# M218A.net
KiCad netlist of a schematic drawn in EAGLE
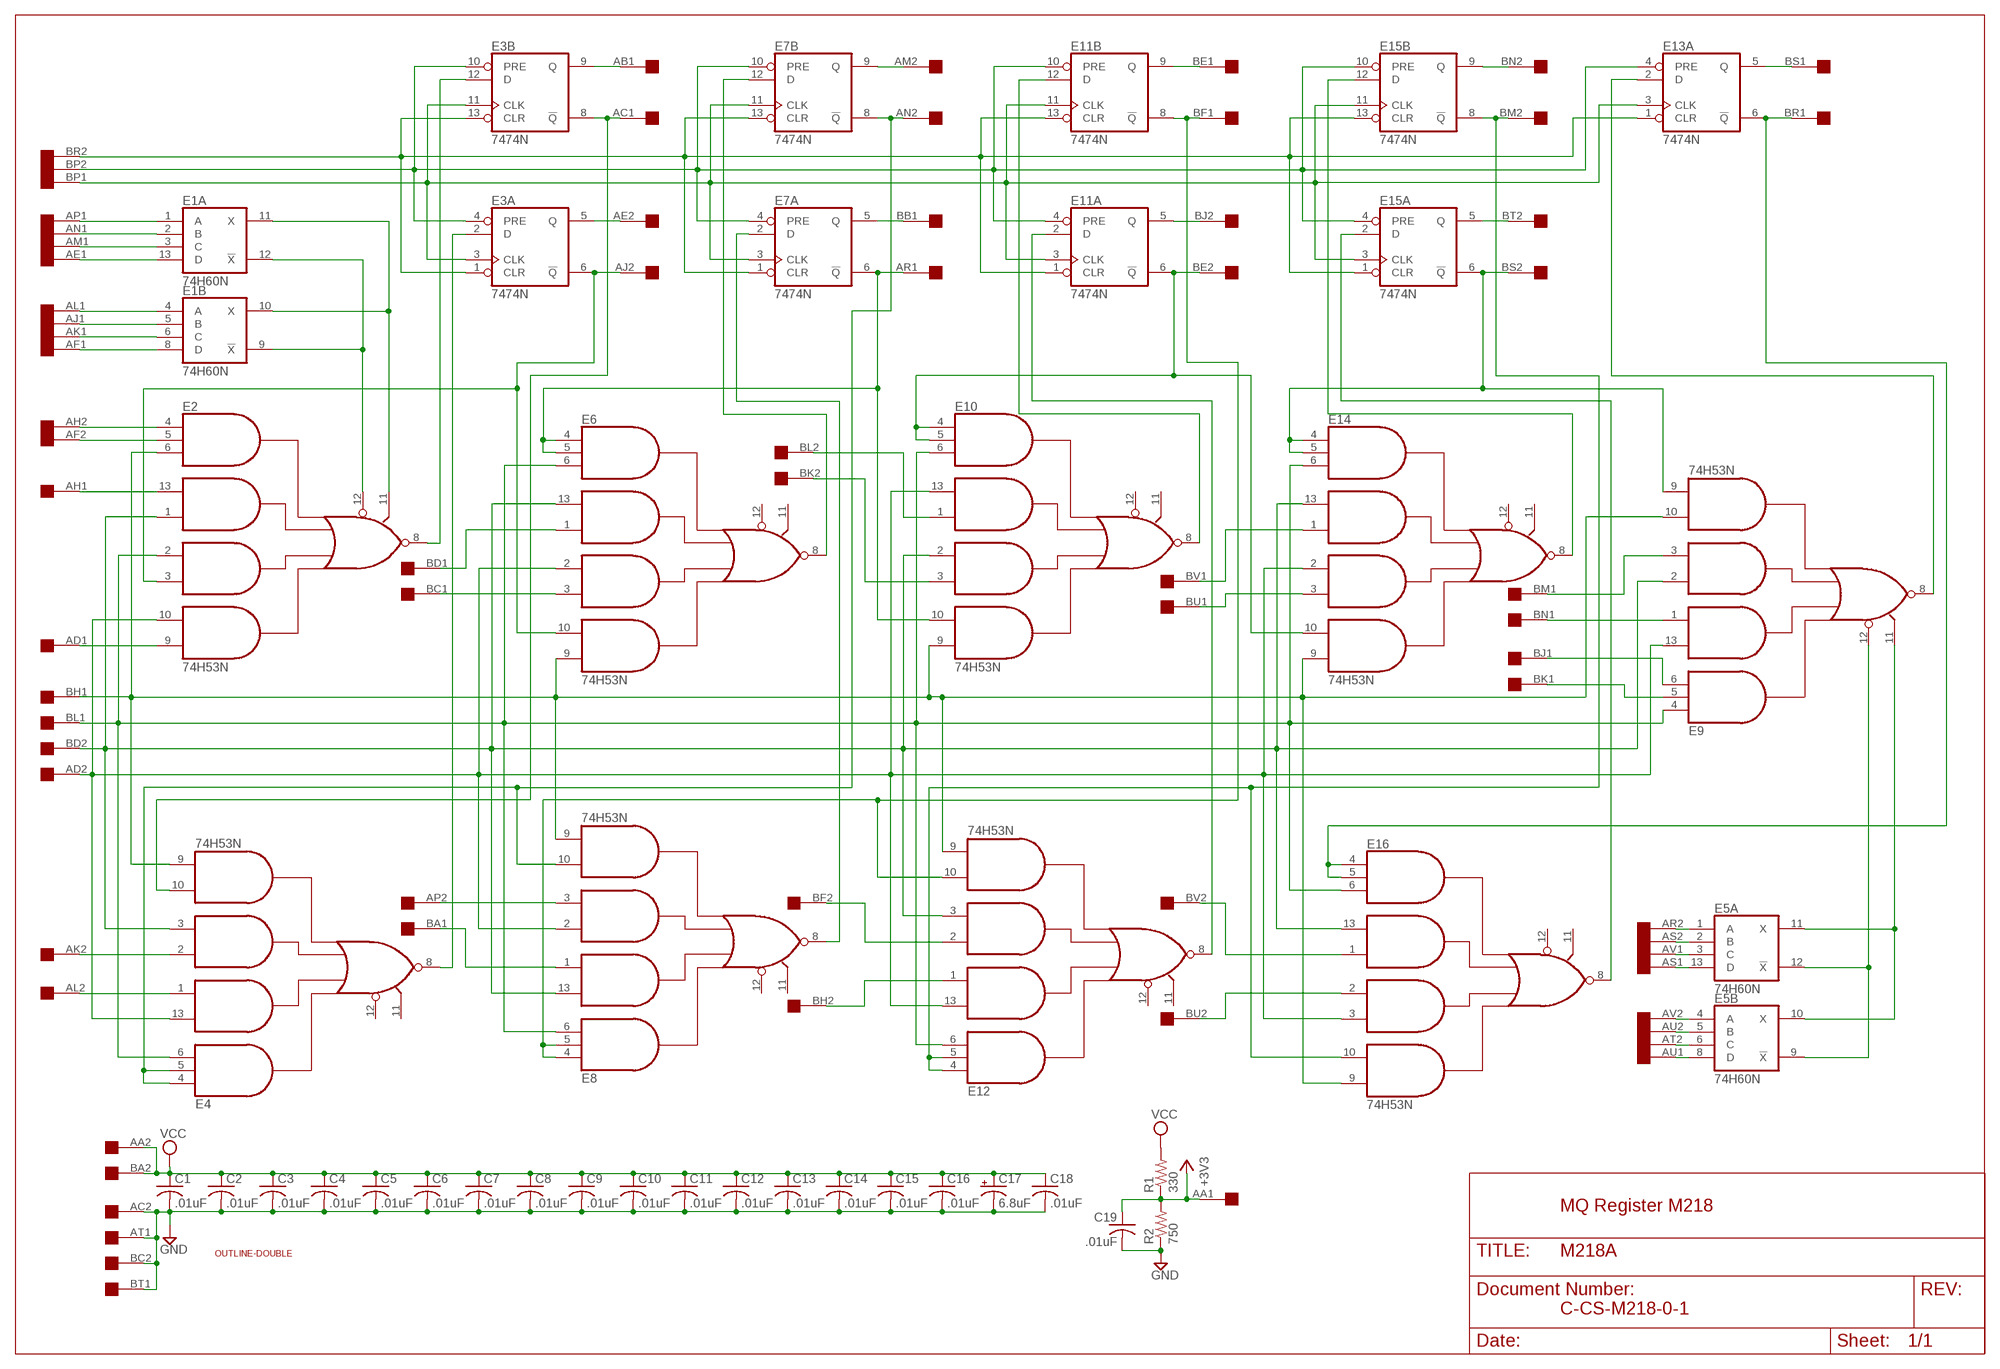
[diagram p0: schematic, sheet 1]

(export (version "E")
  (design (tool "Eeschema 10.0.6"))
  (components
    (comp (ref "C1")
      (value ".01uF")
      (footprint "eagle-import:C050-025X075")
      (libsource (lib "eagle-import") (part "C-US050-025X075"))
    )
    (comp (ref "C2")
      (value ".01uF")
      (footprint "eagle-import:C050-025X075")
      (libsource (lib "eagle-import") (part "C-US050-025X075"))
    )
    (comp (ref "C3")
      (value ".01uF")
      (footprint "eagle-import:C050-025X075")
      (libsource (lib "eagle-import") (part "C-US050-025X075"))
    )
    (comp (ref "C4")
      (value ".01uF")
      (footprint "eagle-import:C050-025X075")
      (libsource (lib "eagle-import") (part "C-US050-025X075"))
    )
    (comp (ref "C5")
      (value ".01uF")
      (footprint "eagle-import:C050-025X075")
      (libsource (lib "eagle-import") (part "C-US050-025X075"))
    )
    (comp (ref "C6")
      (value ".01uF")
      (footprint "eagle-import:C050-025X075")
      (libsource (lib "eagle-import") (part "C-US050-025X075"))
    )
    (comp (ref "C7")
      (value ".01uF")
      (footprint "eagle-import:C050-025X075")
      (libsource (lib "eagle-import") (part "C-US050-025X075"))
    )
    (comp (ref "C8")
      (value ".01uF")
      (footprint "eagle-import:C050-025X075")
      (libsource (lib "eagle-import") (part "C-US050-025X075"))
    )
    (comp (ref "C9")
      (value ".01uF")
      (footprint "eagle-import:C050-025X075")
      (libsource (lib "eagle-import") (part "C-US050-025X075"))
    )
    (comp (ref "C10")
      (value ".01uF")
      (footprint "eagle-import:C050-025X075")
      (libsource (lib "eagle-import") (part "C-US050-025X075"))
    )
    (comp (ref "C11")
      (value ".01uF")
      (footprint "eagle-import:C050-025X075")
      (libsource (lib "eagle-import") (part "C-US050-025X075"))
    )
    (comp (ref "C12")
      (value ".01uF")
      (footprint "eagle-import:C050-025X075")
      (libsource (lib "eagle-import") (part "C-US050-025X075"))
    )
    (comp (ref "C13")
      (value ".01uF")
      (footprint "eagle-import:C050-025X075")
      (libsource (lib "eagle-import") (part "C-US050-025X075"))
    )
    (comp (ref "C14")
      (value ".01uF")
      (footprint "eagle-import:C050-025X075")
      (libsource (lib "eagle-import") (part "C-US050-025X075"))
    )
    (comp (ref "C15")
      (value ".01uF")
      (footprint "eagle-import:C050-025X075")
      (libsource (lib "eagle-import") (part "C-US050-025X075"))
    )
    (comp (ref "C16")
      (value ".01uF")
      (footprint "eagle-import:C050-025X075")
      (libsource (lib "eagle-import") (part "C-US050-025X075"))
    )
    (comp (ref "C17")
      (value "6.8uF")
      (footprint "eagle-import:E12-8")
      (libsource (lib "eagle-import") (part "CPOL-USE20-8AXIAL"))
    )
    (comp (ref "C18")
      (value ".01uF")
      (footprint "eagle-import:C050-025X075")
      (libsource (lib "eagle-import") (part "C-US050-025X075"))
    )
    (comp (ref "C19")
      (value ".01uF")
      (footprint "eagle-import:C050-025X075")
      (libsource (lib "eagle-import") (part "C-US050-025X075"))
    )
    (comp (ref "E1")
      (value "74H60N")
      (footprint "eagle-import:DIL14")
      (libsource (lib "eagle-import") (part "7460N"))
    )
    (comp (ref "E2")
      (value "74H53N")
      (footprint "eagle-import:DIL14")
      (libsource (lib "eagle-import") (part "74H53N"))
    )
    (comp (ref "E3")
      (value "7474N")
      (footprint "eagle-import:DIL14")
      (libsource (lib "eagle-import") (part "7474NS"))
    )
    (comp (ref "E4")
      (value "74H53N")
      (footprint "eagle-import:DIL14")
      (libsource (lib "eagle-import") (part "74H53N"))
    )
    (comp (ref "E5")
      (value "74H60N")
      (footprint "eagle-import:DIL14")
      (libsource (lib "eagle-import") (part "7460N"))
    )
    (comp (ref "E6")
      (value "74H53N")
      (footprint "eagle-import:DIL14")
      (libsource (lib "eagle-import") (part "74H53N"))
    )
    (comp (ref "E7")
      (value "7474N")
      (footprint "eagle-import:DIL14")
      (libsource (lib "eagle-import") (part "7474NS"))
    )
    (comp (ref "E8")
      (value "74H53N")
      (footprint "eagle-import:DIL14")
      (libsource (lib "eagle-import") (part "74H53N"))
    )
    (comp (ref "E9")
      (value "74H53N")
      (footprint "eagle-import:DIL14")
      (libsource (lib "eagle-import") (part "74H53N"))
    )
    (comp (ref "E10")
      (value "74H53N")
      (footprint "eagle-import:DIL14")
      (libsource (lib "eagle-import") (part "74H53N"))
    )
    (comp (ref "E11")
      (value "7474N")
      (footprint "eagle-import:DIL14")
      (libsource (lib "eagle-import") (part "7474NS"))
    )
    (comp (ref "E12")
      (value "74H53N")
      (footprint "eagle-import:DIL14")
      (libsource (lib "eagle-import") (part "74H53N"))
    )
    (comp (ref "E13")
      (value "7474N")
      (footprint "eagle-import:DIL14")
      (libsource (lib "eagle-import") (part "7474NS"))
    )
    (comp (ref "E14")
      (value "74H53N")
      (footprint "eagle-import:DIL14")
      (libsource (lib "eagle-import") (part "74H53N"))
    )
    (comp (ref "E15")
      (value "7474N")
      (footprint "eagle-import:DIL14")
      (libsource (lib "eagle-import") (part "7474NS"))
    )
    (comp (ref "E16")
      (value "74H53N")
      (footprint "eagle-import:DIL14")
      (libsource (lib "eagle-import") (part "74H53N"))
    )
    (comp (ref "R1")
      (value "330")
      (footprint "eagle-import:0207_10")
      (libsource (lib "eagle-import") (part "R-US_0207/10"))
    )
    (comp (ref "R2")
      (value "750")
      (footprint "eagle-import:0207_10")
      (libsource (lib "eagle-import") (part "R-US_0207/10"))
    )
    (comp (ref "U$1")
      (value "OUTLINE-DOUBLE")
      (footprint "eagle-import:DOUBLE")
      (libsource (lib "eagle-import") (part "OUTLINE-DOUBLE"))
    )
    (comp (ref "U$3")
      (value "DOUBLE")
      (footprint "eagle-import:EDGE-CON4")
      (libsource (lib "eagle-import") (part "DOUBLE"))
    )
  )
  (nets
    (net (code "1") (name "+3V3") (class "Default")
      (node (ref "C19") (pin "1") (pinfunction "1_1") (pintype "passive"))
      (node (ref "R1") (pin "1") (pinfunction "1_1") (pintype "passive"))
      (node (ref "R2") (pin "2") (pinfunction "2_2") (pintype "passive"))
      (node (ref "U$3") (pin "AA1") (pinfunction "1_AA1") (pintype "bidirectional"))
    )
    (net (code "2") (name "GND") (class "Default")
      (node (ref "C1") (pin "2") (pinfunction "2_2") (pintype "passive"))
      (node (ref "C10") (pin "2") (pinfunction "2_2") (pintype "passive"))
      (node (ref "C11") (pin "2") (pinfunction "2_2") (pintype "passive"))
      (node (ref "C12") (pin "2") (pinfunction "2_2") (pintype "passive"))
      (node (ref "C13") (pin "2") (pinfunction "2_2") (pintype "passive"))
      (node (ref "C14") (pin "2") (pinfunction "2_2") (pintype "passive"))
      (node (ref "C15") (pin "2") (pinfunction "2_2") (pintype "passive"))
      (node (ref "C16") (pin "2") (pinfunction "2_2") (pintype "passive"))
      (node (ref "C17") (pin "-") (pinfunction "-_-") (pintype "passive"))
      (node (ref "C18") (pin "2") (pinfunction "2_2") (pintype "passive"))
      (node (ref "C19") (pin "2") (pinfunction "2_2") (pintype "passive"))
      (node (ref "C2") (pin "2") (pinfunction "2_2") (pintype "passive"))
      (node (ref "C3") (pin "2") (pinfunction "2_2") (pintype "passive"))
      (node (ref "C4") (pin "2") (pinfunction "2_2") (pintype "passive"))
      (node (ref "C5") (pin "2") (pinfunction "2_2") (pintype "passive"))
      (node (ref "C6") (pin "2") (pinfunction "2_2") (pintype "passive"))
      (node (ref "C7") (pin "2") (pinfunction "2_2") (pintype "passive"))
      (node (ref "C8") (pin "2") (pinfunction "2_2") (pintype "passive"))
      (node (ref "C9") (pin "2") (pinfunction "2_2") (pintype "passive"))
      (node (ref "R2") (pin "1") (pinfunction "1_1") (pintype "passive"))
      (node (ref "U$3") (pin "AC2") (pinfunction "1_AC2") (pintype "bidirectional"))
      (node (ref "U$3") (pin "AT1") (pinfunction "1_AT1") (pintype "bidirectional"))
      (node (ref "U$3") (pin "BC2") (pinfunction "1_BC2") (pintype "bidirectional"))
      (node (ref "U$3") (pin "BT1") (pinfunction "1_BT1") (pintype "bidirectional"))
    )
    (net (code "3") (name "Net-(E1A-A)") (class "Default")
      (node (ref "E1") (pin "1") (pinfunction "A_1") (pintype "input"))
      (node (ref "U$3") (pin "AP1") (pinfunction "1_AP1") (pintype "bidirectional"))
    )
    (net (code "4") (name "Net-(E1A-B)") (class "Default")
      (node (ref "E1") (pin "2") (pinfunction "B_2") (pintype "input"))
      (node (ref "U$3") (pin "AN1") (pinfunction "1_AN1") (pintype "bidirectional"))
    )
    (net (code "5") (name "Net-(E1A-C)") (class "Default")
      (node (ref "E1") (pin "3") (pinfunction "C_3") (pintype "input"))
      (node (ref "U$3") (pin "AM1") (pinfunction "1_AM1") (pintype "bidirectional"))
    )
    (net (code "6") (name "Net-(E1A-D)") (class "Default")
      (node (ref "E1") (pin "13") (pinfunction "D_13") (pintype "input"))
      (node (ref "U$3") (pin "AE1") (pinfunction "1_AE1") (pintype "bidirectional"))
    )
    (net (code "7") (name "Net-(E1A-X)") (class "Default")
      (node (ref "E1") (pin "10") (pinfunction "X_10") (pintype "output"))
      (node (ref "E1") (pin "11") (pinfunction "X_11") (pintype "output"))
      (node (ref "E2") (pin "11") (pinfunction "I10_11") (pintype "passive"))
    )
    (net (code "8") (name "Net-(E1A-~{X})") (class "Default")
      (node (ref "E1") (pin "12") (pinfunction "~{X}_12") (pintype "output"))
      (node (ref "E1") (pin "9") (pinfunction "~{X}_9") (pintype "output"))
      (node (ref "E2") (pin "12") (pinfunction "I9_12") (pintype "passive"))
    )
    (net (code "9") (name "Net-(E1B-A)") (class "Default")
      (node (ref "E1") (pin "4") (pinfunction "A_4") (pintype "input"))
      (node (ref "U$3") (pin "AL1") (pinfunction "1_AL1") (pintype "bidirectional"))
    )
    (net (code "10") (name "Net-(E1B-B)") (class "Default")
      (node (ref "E1") (pin "5") (pinfunction "B_5") (pintype "input"))
      (node (ref "U$3") (pin "AJ1") (pinfunction "1_AJ1") (pintype "bidirectional"))
    )
    (net (code "11") (name "Net-(E1B-C)") (class "Default")
      (node (ref "E1") (pin "6") (pinfunction "C_6") (pintype "input"))
      (node (ref "U$3") (pin "AK1") (pinfunction "1_AK1") (pintype "bidirectional"))
    )
    (net (code "12") (name "Net-(E1B-D)") (class "Default")
      (node (ref "E1") (pin "8") (pinfunction "D_8") (pintype "input"))
      (node (ref "U$3") (pin "AF1") (pinfunction "1_AF1") (pintype "bidirectional"))
    )
    (net (code "13") (name "Net-(E2A-I1)") (class "Default")
      (node (ref "E2") (pin "4") (pinfunction "I1_4") (pintype "input"))
      (node (ref "U$3") (pin "AH2") (pinfunction "1_AH2") (pintype "bidirectional"))
    )
    (net (code "14") (name "Net-(E2A-I3)") (class "Default")
      (node (ref "E2") (pin "13") (pinfunction "I3_13") (pintype "input"))
      (node (ref "U$3") (pin "AH1") (pinfunction "1_AH1") (pintype "bidirectional"))
    )
    (net (code "15") (name "Net-(E2A-I6)") (class "Default")
      (node (ref "E2") (pin "3") (pinfunction "I6_3") (pintype "input"))
      (node (ref "E3") (pin "6") (pinfunction "~{Q}_6") (pintype "output"))
      (node (ref "E6") (pin "10") (pinfunction "I7_10") (pintype "input"))
      (node (ref "U$3") (pin "AJ2") (pinfunction "1_AJ2") (pintype "bidirectional"))
    )
    (net (code "16") (name "Net-(E2A-I8)") (class "Default")
      (node (ref "E2") (pin "9") (pinfunction "I8_9") (pintype "input"))
      (node (ref "U$3") (pin "AD1") (pinfunction "1_AD1") (pintype "bidirectional"))
    )
    (net (code "17") (name "Net-(E2A-I11)") (class "Default")
      (node (ref "E2") (pin "5") (pinfunction "I11_5") (pintype "input"))
      (node (ref "U$3") (pin "AF2") (pinfunction "1_AF2") (pintype "bidirectional"))
    )
    (net (code "18") (name "Net-(E2A-O)") (class "Default")
      (node (ref "E2") (pin "8") (pinfunction "O_8") (pintype "output"))
      (node (ref "E3") (pin "12") (pinfunction "D_12") (pintype "input"))
    )
    (net (code "19") (name "Net-(E3A-D)") (class "Default")
      (node (ref "E3") (pin "2") (pinfunction "D_2") (pintype "input"))
      (node (ref "E4") (pin "8") (pinfunction "O_8") (pintype "output"))
    )
    (net (code "20") (name "Net-(E3A-Q)") (class "Default")
      (node (ref "E3") (pin "5") (pinfunction "Q_5") (pintype "output"))
      (node (ref "U$3") (pin "AE2") (pinfunction "1_AE2") (pintype "bidirectional"))
    )
    (net (code "21") (name "Net-(E3B-Q)") (class "Default")
      (node (ref "E3") (pin "9") (pinfunction "Q_9") (pintype "output"))
      (node (ref "U$3") (pin "AB1") (pinfunction "1_AB1") (pintype "bidirectional"))
    )
    (net (code "22") (name "Net-(E3B-~{Q})") (class "Default")
      (node (ref "E3") (pin "8") (pinfunction "~{Q}_8") (pintype "output"))
      (node (ref "E4") (pin "10") (pinfunction "I7_10") (pintype "input"))
      (node (ref "U$3") (pin "AC1") (pinfunction "1_AC1") (pintype "bidirectional"))
    )
    (net (code "23") (name "Net-(E4A-I1)") (class "Default")
      (node (ref "E4") (pin "4") (pinfunction "I1_4") (pintype "input"))
      (node (ref "E4") (pin "5") (pinfunction "I11_5") (pintype "input"))
      (node (ref "E7") (pin "8") (pinfunction "~{Q}_8") (pintype "output"))
      (node (ref "E8") (pin "10") (pinfunction "I7_10") (pintype "input"))
      (node (ref "U$3") (pin "AN2") (pinfunction "1_AN2") (pintype "bidirectional"))
    )
    (net (code "24") (name "Net-(E4A-I4)") (class "Default")
      (node (ref "E4") (pin "1") (pinfunction "I4_1") (pintype "input"))
      (node (ref "U$3") (pin "AL2") (pinfunction "1_AL2") (pintype "bidirectional"))
    )
    (net (code "25") (name "Net-(E4A-I5)") (class "Default")
      (node (ref "E4") (pin "2") (pinfunction "I5_2") (pintype "input"))
      (node (ref "U$3") (pin "AK2") (pinfunction "1_AK2") (pintype "bidirectional"))
    )
    (net (code "26") (name "Net-(E5A-A)") (class "Default")
      (node (ref "E5") (pin "1") (pinfunction "A_1") (pintype "input"))
      (node (ref "U$3") (pin "AR2") (pinfunction "1_AR2") (pintype "bidirectional"))
    )
    (net (code "27") (name "Net-(E5A-B)") (class "Default")
      (node (ref "E5") (pin "2") (pinfunction "B_2") (pintype "input"))
      (node (ref "U$3") (pin "AS2") (pinfunction "1_AS2") (pintype "bidirectional"))
    )
    (net (code "28") (name "Net-(E5A-C)") (class "Default")
      (node (ref "E5") (pin "3") (pinfunction "C_3") (pintype "input"))
      (node (ref "U$3") (pin "AV1") (pinfunction "1_AV1") (pintype "bidirectional"))
    )
    (net (code "29") (name "Net-(E5A-D)") (class "Default")
      (node (ref "E5") (pin "13") (pinfunction "D_13") (pintype "input"))
      (node (ref "U$3") (pin "AS1") (pinfunction "1_AS1") (pintype "bidirectional"))
    )
    (net (code "30") (name "Net-(E5A-X)") (class "Default")
      (node (ref "E5") (pin "10") (pinfunction "X_10") (pintype "output"))
      (node (ref "E5") (pin "11") (pinfunction "X_11") (pintype "output"))
      (node (ref "E9") (pin "11") (pinfunction "I10_11") (pintype "passive"))
    )
    (net (code "31") (name "Net-(E5A-~{X})") (class "Default")
      (node (ref "E5") (pin "12") (pinfunction "~{X}_12") (pintype "output"))
      (node (ref "E5") (pin "9") (pinfunction "~{X}_9") (pintype "output"))
      (node (ref "E9") (pin "12") (pinfunction "I9_12") (pintype "passive"))
    )
    (net (code "32") (name "Net-(E5B-A)") (class "Default")
      (node (ref "E5") (pin "4") (pinfunction "A_4") (pintype "input"))
      (node (ref "U$3") (pin "AV2") (pinfunction "1_AV2") (pintype "bidirectional"))
    )
    (net (code "33") (name "Net-(E5B-B)") (class "Default")
      (node (ref "E5") (pin "5") (pinfunction "B_5") (pintype "input"))
      (node (ref "U$3") (pin "AU2") (pinfunction "1_AU2") (pintype "bidirectional"))
    )
    (net (code "34") (name "Net-(E5B-C)") (class "Default")
      (node (ref "E5") (pin "6") (pinfunction "C_6") (pintype "input"))
      (node (ref "U$3") (pin "AT2") (pinfunction "1_AT2") (pintype "bidirectional"))
    )
    (net (code "35") (name "Net-(E5B-D)") (class "Default")
      (node (ref "E5") (pin "8") (pinfunction "D_8") (pintype "input"))
      (node (ref "U$3") (pin "AU1") (pinfunction "1_AU1") (pintype "bidirectional"))
    )
    (net (code "36") (name "Net-(E6A-I4)") (class "Default")
      (node (ref "E6") (pin "1") (pinfunction "I4_1") (pintype "input"))
      (node (ref "U$3") (pin "BD1") (pinfunction "1_BD1") (pintype "bidirectional"))
    )
    (net (code "37") (name "Net-(E6A-I6)") (class "Default")
      (node (ref "E6") (pin "3") (pinfunction "I6_3") (pintype "input"))
      (node (ref "U$3") (pin "BC1") (pinfunction "1_BC1") (pintype "bidirectional"))
    )
    (net (code "38") (name "Net-(E6A-O)") (class "Default")
      (node (ref "E6") (pin "8") (pinfunction "O_8") (pintype "output"))
      (node (ref "E7") (pin "12") (pinfunction "D_12") (pintype "input"))
    )
    (net (code "39") (name "Net-(E7A-D)") (class "Default")
      (node (ref "E7") (pin "2") (pinfunction "D_2") (pintype "input"))
      (node (ref "E8") (pin "8") (pinfunction "O_8") (pintype "output"))
    )
    (net (code "40") (name "Net-(E7A-Q)") (class "Default")
      (node (ref "E7") (pin "5") (pinfunction "Q_5") (pintype "output"))
      (node (ref "U$3") (pin "BB1") (pinfunction "1_BB1") (pintype "bidirectional"))
    )
    (net (code "41") (name "Net-(E7B-Q)") (class "Default")
      (node (ref "E7") (pin "9") (pinfunction "Q_9") (pintype "output"))
      (node (ref "U$3") (pin "AM2") (pinfunction "1_AM2") (pintype "bidirectional"))
    )
    (net (code "42") (name "Net-(E8A-I4)") (class "Default")
      (node (ref "E8") (pin "1") (pinfunction "I4_1") (pintype "input"))
      (node (ref "U$3") (pin "BA1") (pinfunction "1_BA1") (pintype "bidirectional"))
    )
    (net (code "43") (name "Net-(E8A-I6)") (class "Default")
      (node (ref "E8") (pin "3") (pinfunction "I6_3") (pintype "input"))
      (node (ref "U$3") (pin "AP2") (pinfunction "1_AP2") (pintype "bidirectional"))
    )
    (net (code "44") (name "Net-(E9A-I2)") (class "Default")
      (node (ref "E9") (pin "6") (pinfunction "I2_6") (pintype "input"))
      (node (ref "U$3") (pin "BJ1") (pinfunction "1_BJ1") (pintype "bidirectional"))
    )
    (net (code "45") (name "Net-(E9A-I4)") (class "Default")
      (node (ref "E9") (pin "1") (pinfunction "I4_1") (pintype "input"))
      (node (ref "U$3") (pin "BN1") (pinfunction "1_BN1") (pintype "bidirectional"))
    )
    (net (code "46") (name "Net-(E9A-I6)") (class "Default")
      (node (ref "E9") (pin "3") (pinfunction "I6_3") (pintype "input"))
      (node (ref "U$3") (pin "BM1") (pinfunction "1_BM1") (pintype "bidirectional"))
    )
    (net (code "47") (name "Net-(E9A-I11)") (class "Default")
      (node (ref "E9") (pin "5") (pinfunction "I11_5") (pintype "input"))
      (node (ref "U$3") (pin "BK1") (pinfunction "1_BK1") (pintype "bidirectional"))
    )
    (net (code "48") (name "Net-(E10A-I1)") (class "Default")
      (node (ref "E10") (pin "4") (pinfunction "I1_4") (pintype "input"))
      (node (ref "E10") (pin "5") (pinfunction "I11_5") (pintype "input"))
      (node (ref "E11") (pin "6") (pinfunction "~{Q}_6") (pintype "output"))
      (node (ref "E14") (pin "10") (pinfunction "I7_10") (pintype "input"))
      (node (ref "U$3") (pin "BE2") (pinfunction "1_BE2") (pintype "bidirectional"))
    )
    (net (code "49") (name "Net-(E10A-I2)") (class "Default")
      (node (ref "E10") (pin "6") (pinfunction "I2_6") (pintype "input"))
      (node (ref "E12") (pin "6") (pinfunction "I2_6") (pintype "input"))
      (node (ref "E14") (pin "6") (pinfunction "I2_6") (pintype "input"))
      (node (ref "E16") (pin "6") (pinfunction "I2_6") (pintype "input"))
      (node (ref "E2") (pin "2") (pinfunction "I5_2") (pintype "input"))
      (node (ref "E4") (pin "6") (pinfunction "I2_6") (pintype "input"))
      (node (ref "E6") (pin "6") (pinfunction "I2_6") (pintype "input"))
      (node (ref "E8") (pin "6") (pinfunction "I2_6") (pintype "input"))
      (node (ref "E9") (pin "4") (pinfunction "I1_4") (pintype "input"))
      (node (ref "U$3") (pin "BL1") (pinfunction "1_BL1") (pintype "bidirectional"))
    )
    (net (code "50") (name "Net-(E10A-I3)") (class "Default")
      (node (ref "E10") (pin "13") (pinfunction "I3_13") (pintype "input"))
      (node (ref "E12") (pin "13") (pinfunction "I3_13") (pintype "input"))
      (node (ref "E14") (pin "2") (pinfunction "I5_2") (pintype "input"))
      (node (ref "E16") (pin "3") (pinfunction "I6_3") (pintype "input"))
      (node (ref "E2") (pin "10") (pinfunction "I7_10") (pintype "input"))
      (node (ref "E4") (pin "13") (pinfunction "I3_13") (pintype "input"))
      (node (ref "E6") (pin "2") (pinfunction "I5_2") (pintype "input"))
      (node (ref "E8") (pin "2") (pinfunction "I5_2") (pintype "input"))
      (node (ref "E9") (pin "13") (pinfunction "I3_13") (pintype "input"))
      (node (ref "U$3") (pin "AD2") (pinfunction "1_AD2") (pintype "bidirectional"))
    )
    (net (code "51") (name "Net-(E10A-I4)") (class "Default")
      (node (ref "E10") (pin "1") (pinfunction "I4_1") (pintype "input"))
      (node (ref "U$3") (pin "BL2") (pinfunction "1_BL2") (pintype "bidirectional"))
    )
    (net (code "52") (name "Net-(E10A-I5)") (class "Default")
      (node (ref "E10") (pin "2") (pinfunction "I5_2") (pintype "input"))
      (node (ref "E12") (pin "3") (pinfunction "I6_3") (pintype "input"))
      (node (ref "E14") (pin "13") (pinfunction "I3_13") (pintype "input"))
      (node (ref "E16") (pin "13") (pinfunction "I3_13") (pintype "input"))
      (node (ref "E2") (pin "1") (pinfunction "I4_1") (pintype "input"))
      (node (ref "E4") (pin "3") (pinfunction "I6_3") (pintype "input"))
      (node (ref "E6") (pin "13") (pinfunction "I3_13") (pintype "input"))
      (node (ref "E8") (pin "13") (pinfunction "I3_13") (pintype "input"))
      (node (ref "E9") (pin "2") (pinfunction "I5_2") (pintype "input"))
      (node (ref "U$3") (pin "BD2") (pinfunction "1_BD2") (pintype "bidirectional"))
    )
    (net (code "53") (name "Net-(E10A-I6)") (class "Default")
      (node (ref "E10") (pin "3") (pinfunction "I6_3") (pintype "input"))
      (node (ref "U$3") (pin "BK2") (pinfunction "1_BK2") (pintype "bidirectional"))
    )
    (net (code "54") (name "Net-(E10A-I7)") (class "Default")
      (node (ref "E10") (pin "10") (pinfunction "I7_10") (pintype "input"))
      (node (ref "E6") (pin "4") (pinfunction "I1_4") (pintype "input"))
      (node (ref "E6") (pin "5") (pinfunction "I11_5") (pintype "input"))
      (node (ref "E7") (pin "6") (pinfunction "~{Q}_6") (pintype "output"))
      (node (ref "U$3") (pin "AR1") (pinfunction "1_AR1") (pintype "bidirectional"))
    )
    (net (code "55") (name "Net-(E10A-I8)") (class "Default")
      (node (ref "E10") (pin "9") (pinfunction "I8_9") (pintype "input"))
      (node (ref "E12") (pin "9") (pinfunction "I8_9") (pintype "input"))
      (node (ref "E14") (pin "9") (pinfunction "I8_9") (pintype "input"))
      (node (ref "E16") (pin "9") (pinfunction "I8_9") (pintype "input"))
      (node (ref "E2") (pin "6") (pinfunction "I2_6") (pintype "input"))
      (node (ref "E4") (pin "9") (pinfunction "I8_9") (pintype "input"))
      (node (ref "E6") (pin "9") (pinfunction "I8_9") (pintype "input"))
      (node (ref "E8") (pin "9") (pinfunction "I8_9") (pintype "input"))
      (node (ref "E9") (pin "10") (pinfunction "I7_10") (pintype "input"))
      (node (ref "U$3") (pin "BH1") (pinfunction "1_BH1") (pintype "bidirectional"))
    )
    (net (code "56") (name "Net-(E10A-O)") (class "Default")
      (node (ref "E10") (pin "8") (pinfunction "O_8") (pintype "output"))
      (node (ref "E11") (pin "12") (pinfunction "D_12") (pintype "input"))
    )
    (net (code "57") (name "Net-(E11A-CLK)") (class "Default")
      (node (ref "E11") (pin "11") (pinfunction "CLK_11") (pintype "input"))
      (node (ref "E11") (pin "3") (pinfunction "CLK_3") (pintype "input"))
      (node (ref "E13") (pin "3") (pinfunction "CLK_3") (pintype "input"))
      (node (ref "E15") (pin "11") (pinfunction "CLK_11") (pintype "input"))
      (node (ref "E15") (pin "3") (pinfunction "CLK_3") (pintype "input"))
      (node (ref "E3") (pin "11") (pinfunction "CLK_11") (pintype "input"))
      (node (ref "E3") (pin "3") (pinfunction "CLK_3") (pintype "input"))
      (node (ref "E7") (pin "11") (pinfunction "CLK_11") (pintype "input"))
      (node (ref "E7") (pin "3") (pinfunction "CLK_3") (pintype "input"))
      (node (ref "U$3") (pin "BP1") (pinfunction "1_BP1") (pintype "bidirectional"))
    )
    (net (code "58") (name "Net-(E11A-CLR)") (class "Default")
      (node (ref "E11") (pin "1") (pinfunction "CLR_1") (pintype "input"))
      (node (ref "E11") (pin "13") (pinfunction "CLR_13") (pintype "input"))
      (node (ref "E13") (pin "1") (pinfunction "CLR_1") (pintype "input"))
      (node (ref "E15") (pin "1") (pinfunction "CLR_1") (pintype "input"))
      (node (ref "E15") (pin "13") (pinfunction "CLR_13") (pintype "input"))
      (node (ref "E3") (pin "1") (pinfunction "CLR_1") (pintype "input"))
      (node (ref "E3") (pin "13") (pinfunction "CLR_13") (pintype "input"))
      (node (ref "E7") (pin "1") (pinfunction "CLR_1") (pintype "input"))
      (node (ref "E7") (pin "13") (pinfunction "CLR_13") (pintype "input"))
      (node (ref "U$3") (pin "BR2") (pinfunction "1_BR2") (pintype "bidirectional"))
    )
    (net (code "59") (name "Net-(E11A-D)") (class "Default")
      (node (ref "E11") (pin "2") (pinfunction "D_2") (pintype "input"))
      (node (ref "E12") (pin "8") (pinfunction "O_8") (pintype "output"))
    )
    (net (code "60") (name "Net-(E11A-PRE)") (class "Default")
      (node (ref "E11") (pin "10") (pinfunction "PRE_10") (pintype "input"))
      (node (ref "E11") (pin "4") (pinfunction "PRE_4") (pintype "input"))
      (node (ref "E13") (pin "4") (pinfunction "PRE_4") (pintype "input"))
      (node (ref "E15") (pin "10") (pinfunction "PRE_10") (pintype "input"))
      (node (ref "E15") (pin "4") (pinfunction "PRE_4") (pintype "input"))
      (node (ref "E3") (pin "10") (pinfunction "PRE_10") (pintype "input"))
      (node (ref "E3") (pin "4") (pinfunction "PRE_4") (pintype "input"))
      (node (ref "E7") (pin "10") (pinfunction "PRE_10") (pintype "input"))
      (node (ref "E7") (pin "4") (pinfunction "PRE_4") (pintype "input"))
      (node (ref "U$3") (pin "BP2") (pinfunction "1_BP2") (pintype "bidirectional"))
    )
    (net (code "61") (name "Net-(E11A-Q)") (class "Default")
      (node (ref "E11") (pin "5") (pinfunction "Q_5") (pintype "output"))
      (node (ref "U$3") (pin "BJ2") (pinfunction "1_BJ2") (pintype "bidirectional"))
    )
    (net (code "62") (name "Net-(E11B-Q)") (class "Default")
      (node (ref "E11") (pin "9") (pinfunction "Q_9") (pintype "output"))
      (node (ref "U$3") (pin "BE1") (pinfunction "1_BE1") (pintype "bidirectional"))
    )
    (net (code "63") (name "Net-(E11B-~{Q})") (class "Default")
      (node (ref "E11") (pin "8") (pinfunction "~{Q}_8") (pintype "output"))
      (node (ref "E12") (pin "10") (pinfunction "I7_10") (pintype "input"))
      (node (ref "E8") (pin "4") (pinfunction "I1_4") (pintype "input"))
      (node (ref "E8") (pin "5") (pinfunction "I11_5") (pintype "input"))
      (node (ref "U$3") (pin "BF1") (pinfunction "1_BF1") (pintype "bidirectional"))
    )
    (net (code "64") (name "Net-(E12A-I1)") (class "Default")
      (node (ref "E12") (pin "4") (pinfunction "I1_4") (pintype "input"))
      (node (ref "E12") (pin "5") (pinfunction "I11_5") (pintype "input"))
      (node (ref "E15") (pin "8") (pinfunction "~{Q}_8") (pintype "output"))
      (node (ref "E16") (pin "10") (pinfunction "I7_10") (pintype "input"))
      (node (ref "U$3") (pin "BM2") (pinfunction "1_BM2") (pintype "bidirectional"))
    )
    (net (code "65") (name "Net-(E12A-I4)") (class "Default")
      (node (ref "E12") (pin "1") (pinfunction "I4_1") (pintype "input"))
      (node (ref "U$3") (pin "BH2") (pinfunction "1_BH2") (pintype "bidirectional"))
    )
    (net (code "66") (name "Net-(E12A-I5)") (class "Default")
      (node (ref "E12") (pin "2") (pinfunction "I5_2") (pintype "input"))
      (node (ref "U$3") (pin "BF2") (pinfunction "1_BF2") (pintype "bidirectional"))
    )
    (net (code "67") (name "Net-(E13A-D)") (class "Default")
      (node (ref "E13") (pin "2") (pinfunction "D_2") (pintype "input"))
      (node (ref "E9") (pin "8") (pinfunction "O_8") (pintype "output"))
    )
    (net (code "68") (name "Net-(E13A-Q)") (class "Default")
      (node (ref "E13") (pin "5") (pinfunction "Q_5") (pintype "output"))
      (node (ref "U$3") (pin "BS1") (pinfunction "1_BS1") (pintype "bidirectional"))
    )
    (net (code "69") (name "Net-(E13A-~{Q})") (class "Default")
      (node (ref "E13") (pin "6") (pinfunction "~{Q}_6") (pintype "output"))
      (node (ref "E16") (pin "4") (pinfunction "I1_4") (pintype "input"))
      (node (ref "E16") (pin "5") (pinfunction "I11_5") (pintype "input"))
      (node (ref "U$3") (pin "BR1") (pinfunction "1_BR1") (pintype "bidirectional"))
    )
    (net (code "70") (name "Net-(E14A-I1)") (class "Default")
      (node (ref "E14") (pin "4") (pinfunction "I1_4") (pintype "input"))
      (node (ref "E14") (pin "5") (pinfunction "I11_5") (pintype "input"))
      (node (ref "E15") (pin "6") (pinfunction "~{Q}_6") (pintype "output"))
      (node (ref "E9") (pin "9") (pinfunction "I8_9") (pintype "input"))
      (node (ref "U$3") (pin "BS2") (pinfunction "1_BS2") (pintype "bidirectional"))
    )
    (net (code "71") (name "Net-(E14A-I4)") (class "Default")
      (node (ref "E14") (pin "1") (pinfunction "I4_1") (pintype "input"))
      (node (ref "U$3") (pin "BV1") (pinfunction "1_BV1") (pintype "bidirectional"))
    )
    (net (code "72") (name "Net-(E14A-I6)") (class "Default")
      (node (ref "E14") (pin "3") (pinfunction "I6_3") (pintype "input"))
      (node (ref "U$3") (pin "BU1") (pinfunction "1_BU1") (pintype "bidirectional"))
    )
    (net (code "73") (name "Net-(E14A-O)") (class "Default")
      (node (ref "E14") (pin "8") (pinfunction "O_8") (pintype "output"))
      (node (ref "E15") (pin "12") (pinfunction "D_12") (pintype "input"))
    )
    (net (code "74") (name "Net-(E15A-D)") (class "Default")
      (node (ref "E15") (pin "2") (pinfunction "D_2") (pintype "input"))
      (node (ref "E16") (pin "8") (pinfunction "O_8") (pintype "output"))
    )
    (net (code "75") (name "Net-(E15A-Q)") (class "Default")
      (node (ref "E15") (pin "5") (pinfunction "Q_5") (pintype "output"))
      (node (ref "U$3") (pin "BT2") (pinfunction "1_BT2") (pintype "bidirectional"))
    )
    (net (code "76") (name "Net-(E15B-Q)") (class "Default")
      (node (ref "E15") (pin "9") (pinfunction "Q_9") (pintype "output"))
      (node (ref "U$3") (pin "BN2") (pinfunction "1_BN2") (pintype "bidirectional"))
    )
    (net (code "77") (name "Net-(E16A-I4)") (class "Default")
      (node (ref "E16") (pin "1") (pinfunction "I4_1") (pintype "input"))
      (node (ref "U$3") (pin "BV2") (pinfunction "1_BV2") (pintype "bidirectional"))
    )
    (net (code "78") (name "Net-(E16A-I5)") (class "Default")
      (node (ref "E16") (pin "2") (pinfunction "I5_2") (pintype "input"))
      (node (ref "U$3") (pin "BU2") (pinfunction "1_BU2") (pintype "bidirectional"))
    )
    (net (code "79") (name "VCC") (class "Default")
      (node (ref "C1") (pin "1") (pinfunction "1_1") (pintype "passive"))
      (node (ref "C10") (pin "1") (pinfunction "1_1") (pintype "passive"))
      (node (ref "C11") (pin "1") (pinfunction "1_1") (pintype "passive"))
      (node (ref "C12") (pin "1") (pinfunction "1_1") (pintype "passive"))
      (node (ref "C13") (pin "1") (pinfunction "1_1") (pintype "passive"))
      (node (ref "C14") (pin "1") (pinfunction "1_1") (pintype "passive"))
      (node (ref "C15") (pin "1") (pinfunction "1_1") (pintype "passive"))
      (node (ref "C16") (pin "1") (pinfunction "1_1") (pintype "passive"))
      (node (ref "C17") (pin "+") (pinfunction "+_+") (pintype "passive"))
      (node (ref "C18") (pin "1") (pinfunction "1_1") (pintype "passive"))
      (node (ref "C2") (pin "1") (pinfunction "1_1") (pintype "passive"))
      (node (ref "C3") (pin "1") (pinfunction "1_1") (pintype "passive"))
      (node (ref "C4") (pin "1") (pinfunction "1_1") (pintype "passive"))
      (node (ref "C5") (pin "1") (pinfunction "1_1") (pintype "passive"))
      (node (ref "C6") (pin "1") (pinfunction "1_1") (pintype "passive"))
      (node (ref "C7") (pin "1") (pinfunction "1_1") (pintype "passive"))
      (node (ref "C8") (pin "1") (pinfunction "1_1") (pintype "passive"))
      (node (ref "C9") (pin "1") (pinfunction "1_1") (pintype "passive"))
      (node (ref "R1") (pin "2") (pinfunction "2_2") (pintype "passive"))
      (node (ref "U$3") (pin "AA2") (pinfunction "1_AA2") (pintype "bidirectional"))
      (node (ref "U$3") (pin "BA2") (pinfunction "1_BA2") (pintype "bidirectional"))
    )
    (net (code "80") (name "unconnected-(E4A-I9-Pad12)") (class "Default")
      (node (ref "E4") (pin "12") (pinfunction "I9_12") (pintype "passive"))
    )
    (net (code "81") (name "unconnected-(E4A-I10-Pad11)") (class "Default")
      (node (ref "E4") (pin "11") (pinfunction "I10_11") (pintype "passive"))
    )
    (net (code "82") (name "unconnected-(E6A-I9-Pad12)") (class "Default")
      (node (ref "E6") (pin "12") (pinfunction "I9_12") (pintype "passive"))
    )
    (net (code "83") (name "unconnected-(E6A-I10-Pad11)") (class "Default")
      (node (ref "E6") (pin "11") (pinfunction "I10_11") (pintype "passive"))
    )
    (net (code "84") (name "unconnected-(E8A-I9-Pad12)") (class "Default")
      (node (ref "E8") (pin "12") (pinfunction "I9_12") (pintype "passive"))
    )
    (net (code "85") (name "unconnected-(E8A-I10-Pad11)") (class "Default")
      (node (ref "E8") (pin "11") (pinfunction "I10_11") (pintype "passive"))
    )
    (net (code "86") (name "unconnected-(E10A-I9-Pad12)") (class "Default")
      (node (ref "E10") (pin "12") (pinfunction "I9_12") (pintype "passive"))
    )
    (net (code "87") (name "unconnected-(E10A-I10-Pad11)") (class "Default")
      (node (ref "E10") (pin "11") (pinfunction "I10_11") (pintype "passive"))
    )
    (net (code "88") (name "unconnected-(E12A-I9-Pad12)") (class "Default")
      (node (ref "E12") (pin "12") (pinfunction "I9_12") (pintype "passive"))
    )
    (net (code "89") (name "unconnected-(E12A-I10-Pad11)") (class "Default")
      (node (ref "E12") (pin "11") (pinfunction "I10_11") (pintype "passive"))
    )
    (net (code "90") (name "unconnected-(E14A-I9-Pad12)") (class "Default")
      (node (ref "E14") (pin "12") (pinfunction "I9_12") (pintype "passive"))
    )
    (net (code "91") (name "unconnected-(E14A-I10-Pad11)") (class "Default")
      (node (ref "E14") (pin "11") (pinfunction "I10_11") (pintype "passive"))
    )
    (net (code "92") (name "unconnected-(E16A-I9-Pad12)") (class "Default")
      (node (ref "E16") (pin "12") (pinfunction "I9_12") (pintype "passive"))
    )
    (net (code "93") (name "unconnected-(E16A-I10-Pad11)") (class "Default")
      (node (ref "E16") (pin "11") (pinfunction "I10_11") (pintype "passive"))
    )
  )
)
